# Rs232Iso-v1_1.net
KiCad netlist of a schematic drawn in EAGLE
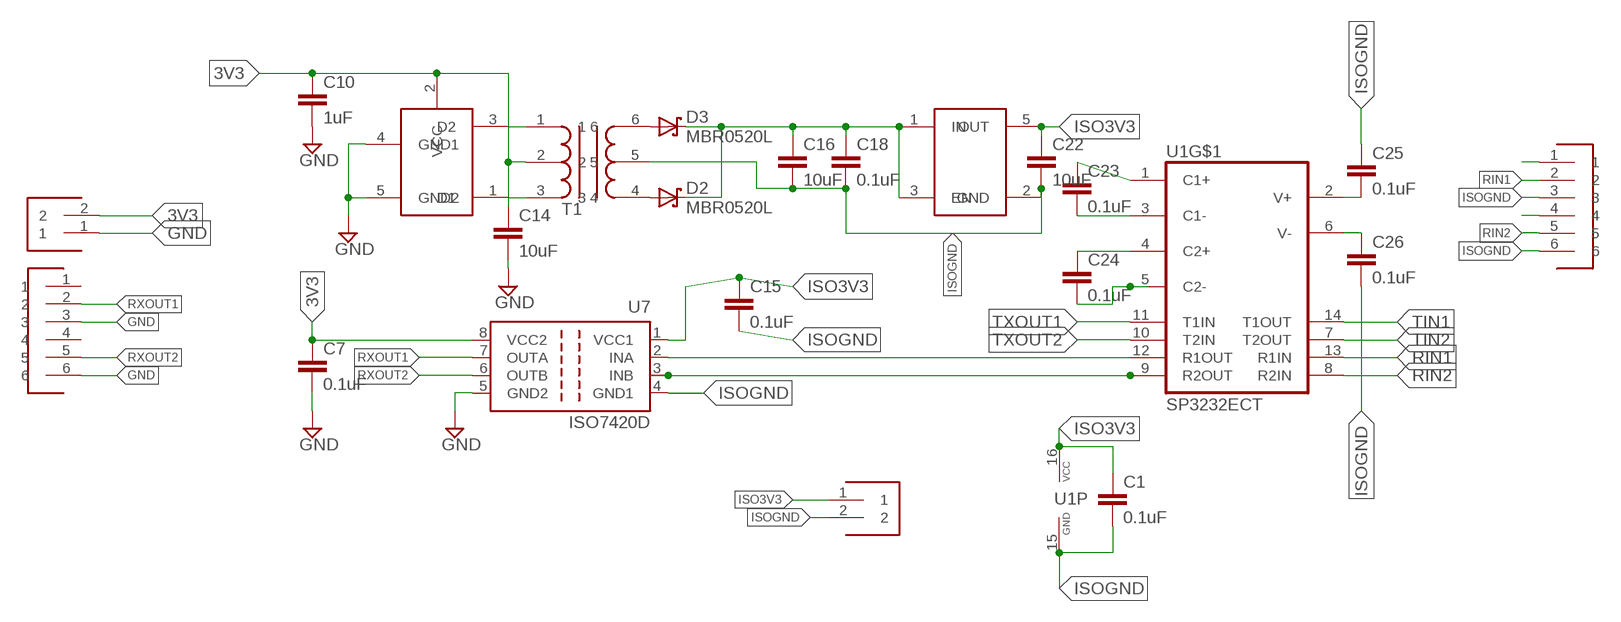
[diagram p0: schematic, sheet 1]

(export (version "E")
  (design (tool "Eeschema 10.0.6"))
  (components
    (comp (ref "C1")
      (value "0.1uF")
      (footprint "eagle-import:0805")
      (libsource (lib "eagle-import") (part "CAP0805"))
    )
    (comp (ref "C7")
      (value "0.1uF")
      (footprint "eagle-import:0805")
      (libsource (lib "eagle-import") (part "CAP0805"))
    )
    (comp (ref "C10")
      (value "1uF")
      (footprint "eagle-import:0805")
      (libsource (lib "eagle-import") (part "CAP0805"))
    )
    (comp (ref "C14")
      (value "10uF")
      (footprint "eagle-import:0805")
      (libsource (lib "eagle-import") (part "CAP0805"))
    )
    (comp (ref "C15")
      (value "0.1uF")
      (footprint "eagle-import:0805")
      (libsource (lib "eagle-import") (part "CAP0805"))
    )
    (comp (ref "C16")
      (value "10uF")
      (footprint "eagle-import:0805")
      (libsource (lib "eagle-import") (part "CAP0805"))
    )
    (comp (ref "C18")
      (value "0.1uF")
      (footprint "eagle-import:0805")
      (libsource (lib "eagle-import") (part "CAP0805"))
    )
    (comp (ref "C22")
      (value "10uF")
      (footprint "eagle-import:0805")
      (libsource (lib "eagle-import") (part "CAP0805"))
    )
    (comp (ref "C23")
      (value "0.1uF")
      (footprint "eagle-import:0805")
      (libsource (lib "eagle-import") (part "CAP0805"))
    )
    (comp (ref "C24")
      (value "0.1uF")
      (footprint "eagle-import:0805")
      (libsource (lib "eagle-import") (part "CAP0805"))
    )
    (comp (ref "C25")
      (value "0.1uF")
      (footprint "eagle-import:0805")
      (libsource (lib "eagle-import") (part "CAP0805"))
    )
    (comp (ref "C26")
      (value "0.1uF")
      (footprint "eagle-import:0805")
      (libsource (lib "eagle-import") (part "CAP0805"))
    )
    (comp (ref "D2")
      (value "MBR0520L")
      (footprint "eagle-import:SOD123")
      (libsource (lib "eagle-import") (part "MBR0520L"))
    )
    (comp (ref "D3")
      (value "MBR0520L")
      (footprint "eagle-import:SOD123")
      (libsource (lib "eagle-import") (part "MBR0520L"))
    )
    (comp (ref "J1")
      (value "CON-2")
      (footprint "eagle-import:CON-2")
      (libsource (lib "eagle-import") (part "CON-2"))
    )
    (comp (ref "J2")
      (value "CON-6")
      (footprint "eagle-import:CON-6")
      (libsource (lib "eagle-import") (part "CON-6"))
    )
    (comp (ref "J3")
      (value "CON-2")
      (footprint "eagle-import:CON-2")
      (libsource (lib "eagle-import") (part "CON-2"))
    )
    (comp (ref "J4")
      (value "CON-6")
      (footprint "eagle-import:CON-6")
      (libsource (lib "eagle-import") (part "CON-6"))
    )
    (comp (ref "T1")
      (value "WE-PP-ISO-TRANSFORMER760390014")
      (footprint "eagle-import:WE_TRANSFORMER")
      (libsource (lib "eagle-import") (part "WE-PP-ISO-TRANSFORMER760390014"))
    )
    (comp (ref "U1")
      (value "SP3232ECT")
      (footprint "eagle-import:SO16")
      (libsource (lib "eagle-import") (part "SP3232ECT"))
    )
    (comp (ref "U2")
      (value "TPS76333")
      (footprint "eagle-import:SOT23-5L")
      (libsource (lib "eagle-import") (part "TPS76333"))
    )
    (comp (ref "U5")
      (value "SN6501DBVT")
      (footprint "eagle-import:SOT23-5L")
      (libsource (lib "eagle-import") (part "SN6501DBVT"))
    )
    (comp (ref "U7")
      (value "ISO7420D")
      (footprint "eagle-import:SO08")
      (libsource (lib "eagle-import") (part "ISO7420D"))
    )
  )
  (nets
    (net (code "1") (name "3V3") (class "Default")
      (node (ref "C10") (pin "1") (pinfunction "1_1") (pintype "passive"))
      (node (ref "C14") (pin "1") (pinfunction "1_1") (pintype "passive"))
      (node (ref "C7") (pin "1") (pinfunction "1_1") (pintype "passive"))
      (node (ref "J1") (pin "2") (pinfunction "2_2") (pintype "bidirectional"))
      (node (ref "T1") (pin "2") (pinfunction "2_2") (pintype "input"))
      (node (ref "U5") (pin "2") (pinfunction "VCC_2") (pintype "bidirectional"))
      (node (ref "U7") (pin "8") (pinfunction "VCC2_8") (pintype "power_in"))
    )
    (net (code "2") (name "GND") (class "Default")
      (node (ref "C10") (pin "2") (pinfunction "2_2") (pintype "passive"))
      (node (ref "C14") (pin "2") (pinfunction "2_2") (pintype "passive"))
      (node (ref "C7") (pin "2") (pinfunction "2_2") (pintype "passive"))
      (node (ref "J1") (pin "1") (pinfunction "1_1") (pintype "bidirectional"))
      (node (ref "J4") (pin "3") (pinfunction "3_3") (pintype "bidirectional"))
      (node (ref "J4") (pin "6") (pinfunction "6_6") (pintype "bidirectional"))
      (node (ref "U5") (pin "4") (pinfunction "GND1_4") (pintype "bidirectional"))
      (node (ref "U5") (pin "5") (pinfunction "GND2_5") (pintype "bidirectional"))
      (node (ref "U7") (pin "5") (pinfunction "GND2_5") (pintype "power_in"))
    )
    (net (code "3") (name "ISO3V3") (class "Default")
      (node (ref "C1") (pin "1") (pinfunction "1_1") (pintype "passive"))
      (node (ref "C15") (pin "1") (pinfunction "1_1") (pintype "passive"))
      (node (ref "C22") (pin "1") (pinfunction "1_1") (pintype "passive"))
      (node (ref "J3") (pin "1") (pinfunction "1_1") (pintype "bidirectional"))
      (node (ref "U1") (pin "16") (pinfunction "VCC_16") (pintype "power_in"))
      (node (ref "U2") (pin "5") (pinfunction "OUT_5") (pintype "bidirectional"))
      (node (ref "U7") (pin "1") (pinfunction "VCC1_1") (pintype "power_in"))
    )
    (net (code "4") (name "ISOGND") (class "Default")
      (node (ref "C1") (pin "2") (pinfunction "2_2") (pintype "passive"))
      (node (ref "C15") (pin "2") (pinfunction "2_2") (pintype "passive"))
      (node (ref "C16") (pin "2") (pinfunction "2_2") (pintype "passive"))
      (node (ref "C18") (pin "2") (pinfunction "2_2") (pintype "passive"))
      (node (ref "C22") (pin "2") (pinfunction "2_2") (pintype "passive"))
      (node (ref "C25") (pin "1") (pinfunction "1_1") (pintype "passive"))
      (node (ref "C26") (pin "2") (pinfunction "2_2") (pintype "passive"))
      (node (ref "J2") (pin "3") (pinfunction "3_3") (pintype "bidirectional"))
      (node (ref "J2") (pin "6") (pinfunction "6_6") (pintype "bidirectional"))
      (node (ref "J3") (pin "2") (pinfunction "2_2") (pintype "bidirectional"))
      (node (ref "T1") (pin "5") (pinfunction "5_5") (pintype "passive"))
      (node (ref "U1") (pin "15") (pinfunction "GND_15") (pintype "power_in"))
      (node (ref "U2") (pin "2") (pinfunction "GND_2") (pintype "bidirectional"))
      (node (ref "U7") (pin "4") (pinfunction "GND1_4") (pintype "power_in"))
    )
    (net (code "5") (name "Net-(D2-PadA)") (class "Default")
      (node (ref "D2") (pin "A") (pinfunction "A_A") (pintype "passive"))
      (node (ref "T1") (pin "4") (pinfunction "4_4") (pintype "passive"))
    )
    (net (code "6") (name "Net-(D3-PadA)") (class "Default")
      (node (ref "D3") (pin "A") (pinfunction "A_A") (pintype "passive"))
      (node (ref "T1") (pin "6") (pinfunction "6_6") (pintype "passive"))
    )
    (net (code "7") (name "Net-(U1A-C1+)") (class "Default")
      (node (ref "C23") (pin "1") (pinfunction "1_1") (pintype "passive"))
      (node (ref "U1") (pin "1") (pinfunction "C1+_1") (pintype "bidirectional"))
    )
    (net (code "8") (name "Net-(U1A-C1-)") (class "Default")
      (node (ref "C23") (pin "2") (pinfunction "2_2") (pintype "passive"))
      (node (ref "U1") (pin "3") (pinfunction "C1-_3") (pintype "bidirectional"))
    )
    (net (code "9") (name "Net-(U1A-C2+)") (class "Default")
      (node (ref "C24") (pin "1") (pinfunction "1_1") (pintype "passive"))
      (node (ref "U1") (pin "4") (pinfunction "C2+_4") (pintype "bidirectional"))
    )
    (net (code "10") (name "Net-(U1A-C2-)") (class "Default")
      (node (ref "C24") (pin "2") (pinfunction "2_2") (pintype "passive"))
      (node (ref "U1") (pin "5") (pinfunction "C2-_5") (pintype "bidirectional"))
    )
    (net (code "11") (name "Net-(U1A-R1OUT)") (class "Default")
      (node (ref "U1") (pin "12") (pinfunction "R1OUT_12") (pintype "output"))
      (node (ref "U7") (pin "2") (pinfunction "INA_2") (pintype "input"))
    )
    (net (code "12") (name "Net-(U1A-R2OUT)") (class "Default")
      (node (ref "U1") (pin "9") (pinfunction "R2OUT_9") (pintype "output"))
      (node (ref "U7") (pin "3") (pinfunction "INB_3") (pintype "input"))
    )
    (net (code "13") (name "Net-(U1A-V+)") (class "Default")
      (node (ref "C25") (pin "2") (pinfunction "2_2") (pintype "passive"))
      (node (ref "U1") (pin "2") (pinfunction "V+_2") (pintype "bidirectional"))
    )
    (net (code "14") (name "Net-(U1A-V-)") (class "Default")
      (node (ref "C26") (pin "1") (pinfunction "1_1") (pintype "passive"))
      (node (ref "U1") (pin "6") (pinfunction "V-_6") (pintype "bidirectional"))
    )
    (net (code "15") (name "Net-(U2-EN)") (class "Default")
      (node (ref "C16") (pin "1") (pinfunction "1_1") (pintype "passive"))
      (node (ref "C18") (pin "1") (pinfunction "1_1") (pintype "passive"))
      (node (ref "D2") (pin "C") (pinfunction "C_C") (pintype "passive"))
      (node (ref "D3") (pin "C") (pinfunction "C_C") (pintype "passive"))
      (node (ref "U2") (pin "1") (pinfunction "IN_1") (pintype "bidirectional"))
      (node (ref "U2") (pin "3") (pinfunction "EN_3") (pintype "bidirectional"))
    )
    (net (code "16") (name "Net-(U5-D1)") (class "Default")
      (node (ref "T1") (pin "3") (pinfunction "3_3") (pintype "input"))
      (node (ref "U5") (pin "1") (pinfunction "D1_1") (pintype "bidirectional"))
    )
    (net (code "17") (name "Net-(U5-D2)") (class "Default")
      (node (ref "T1") (pin "1") (pinfunction "1_1") (pintype "input"))
      (node (ref "U5") (pin "3") (pinfunction "D2_3") (pintype "bidirectional"))
    )
    (net (code "18") (name "RIN1") (class "Default")
      (node (ref "J2") (pin "2") (pinfunction "2_2") (pintype "bidirectional"))
      (node (ref "U1") (pin "13") (pinfunction "R1IN_13") (pintype "input"))
    )
    (net (code "19") (name "RIN2") (class "Default")
      (node (ref "J2") (pin "5") (pinfunction "5_5") (pintype "bidirectional"))
      (node (ref "U1") (pin "8") (pinfunction "R2IN_8") (pintype "input"))
    )
    (net (code "20") (name "RXOUT1") (class "Default")
      (node (ref "J4") (pin "2") (pinfunction "2_2") (pintype "bidirectional"))
      (node (ref "U7") (pin "7") (pinfunction "OUTA_7") (pintype "output"))
    )
    (net (code "21") (name "RXOUT2") (class "Default")
      (node (ref "J4") (pin "5") (pinfunction "5_5") (pintype "bidirectional"))
      (node (ref "U7") (pin "6") (pinfunction "OUTB_6") (pintype "output"))
    )
    (net (code "22") (name "TIN1") (class "Default")
      (node (ref "U1") (pin "14") (pinfunction "T1OUT_14") (pintype "output"))
    )
    (net (code "23") (name "TIN2") (class "Default")
      (node (ref "U1") (pin "7") (pinfunction "T2OUT_7") (pintype "output"))
    )
    (net (code "24") (name "TXOUT1") (class "Default")
      (node (ref "U1") (pin "11") (pinfunction "T1IN_11") (pintype "input"))
    )
    (net (code "25") (name "TXOUT2") (class "Default")
      (node (ref "U1") (pin "10") (pinfunction "T2IN_10") (pintype "input"))
    )
    (net (code "26") (name "unconnected-(J2-Pad1)") (class "Default")
      (node (ref "J2") (pin "1") (pinfunction "1_1") (pintype "bidirectional"))
    )
    (net (code "27") (name "unconnected-(J2-Pad4)") (class "Default")
      (node (ref "J2") (pin "4") (pinfunction "4_4") (pintype "bidirectional"))
    )
    (net (code "28") (name "unconnected-(J4-Pad1)") (class "Default")
      (node (ref "J4") (pin "1") (pinfunction "1_1") (pintype "bidirectional"))
    )
    (net (code "29") (name "unconnected-(J4-Pad4)") (class "Default")
      (node (ref "J4") (pin "4") (pinfunction "4_4") (pintype "bidirectional"))
    )
  )
)
